# sherpa_1a_minimal_template.net
KiCad netlist of a schematic drawn in Altium Designer
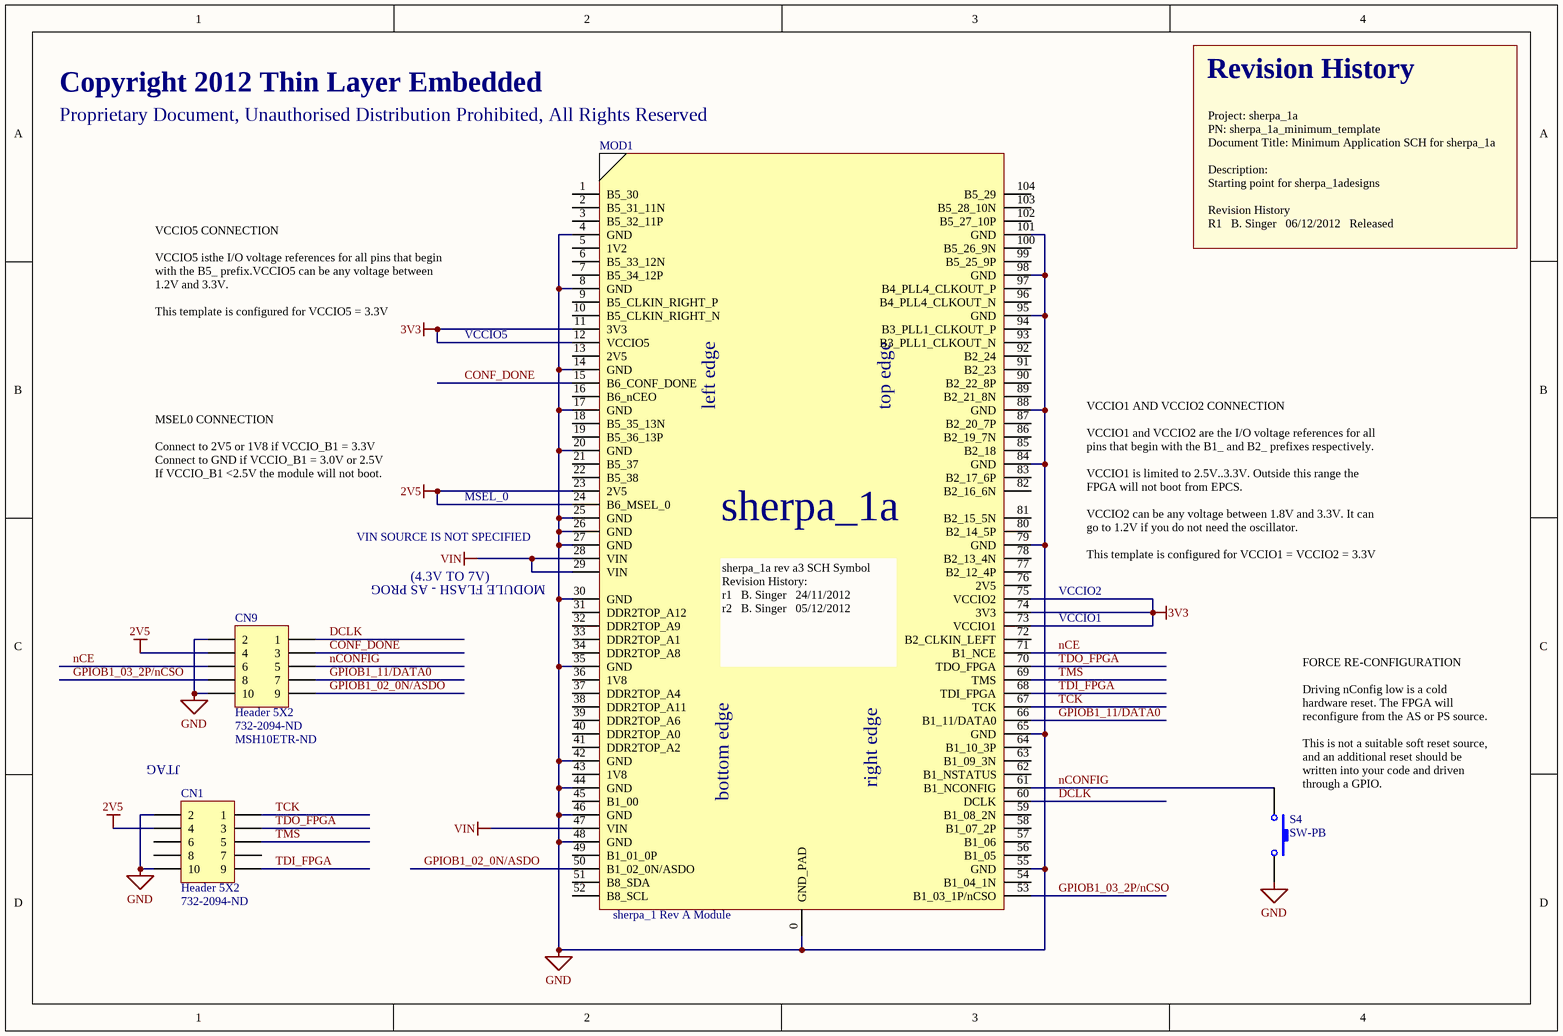
[diagram p0: sherpa_1a_minimal_template.SchDoc]

(export (version "E")
  (design (tool "Eeschema 10.0.6"))
  (components
    (comp (ref "CN1")
      (value "Header 5X2")
      (footprint "BOXHDR2X5_SMT")
      (description "Header, 5-Pin, Dual row")
      (fields
        (field (name "SUPPLIER PART NUMBER 1") "732-2094-ND")
        (field (name "MANUFACTURER") "Wurth Electronics Inc")
        (field (name "MANUFACTURER PART NUMBER") "61201021621")
        (field (name "PUBLISHER") "Altium Limited")
      )
      (libsource (lib "Miscellaneous Connectors") (part "Header 5X2"))
    )
    (comp (ref "CN9")
      (value "Header 5X2")
      (footprint "BOXHDR2X5_SMT")
      (description "Header, 5-Pin, Dual row")
      (fields
        (field (name "SUPPLIER PART NUMBER 1") "732-2094-ND")
        (field (name "MANUFACTURER") "Wurth Electronics Inc")
        (field (name "MANUFACTURER PART NUMBER") "61201021621")
        (field (name "SUPPLIER PART NUMBER 2") "MSH10ETR-ND")
        (field (name "PUBLISHER") "Altium Limited")
      )
      (libsource (lib "Miscellaneous Connectors") (part "Header 5X2"))
    )
    (comp (ref "MOD1")
      (value "sherpa_1 Rev A Module")
      (footprint "MODULE")
      (libsource (lib "master_library") (part "sherpa_1 Rev A Module"))
    )
    (comp (ref "S4")
      (value "SW-PB")
      (footprint "TL1105_V")
      (description "Switch")
      (fields (field (name "PUBLISHER") "Altium Limited"))
      (libsource (lib "Miscellaneous Devices") (part "SW-PB"))
    )
  )
  (nets
    (net (code "1") (name "/CONF_DONE") (class "Default")
      (node (ref "CN9") (pin "3") (pinfunction "3_3") (pintype "passive"))
      (node (ref "MOD1") (pin "15") (pinfunction "B6_CONF_DONE_15") (pintype "passive"))
    )
    (net (code "2") (name "/DCLK") (class "Default")
      (node (ref "CN9") (pin "1") (pinfunction "1_1") (pintype "passive"))
      (node (ref "MOD1") (pin "60") (pinfunction "DCLK_60") (pintype "passive"))
    )
    (net (code "3") (name "/GPIOB1_02_0N{slash}ASDO") (class "Default")
      (node (ref "CN9") (pin "9") (pinfunction "9_9") (pintype "passive"))
      (node (ref "MOD1") (pin "50") (pinfunction "B1_02_0N/ASDO_50") (pintype "passive"))
    )
    (net (code "4") (name "/GPIOB1_03_2P{slash}nCSO") (class "Default")
      (node (ref "CN9") (pin "8") (pinfunction "8_8") (pintype "passive"))
      (node (ref "MOD1") (pin "53") (pinfunction "B1_03_1P/nCSO_53") (pintype "passive"))
    )
    (net (code "5") (name "/GPIOB1_11{slash}DATA0") (class "Default")
      (node (ref "CN9") (pin "7") (pinfunction "7_7") (pintype "passive"))
      (node (ref "MOD1") (pin "66") (pinfunction "B1_11/DATA0_66") (pintype "passive"))
    )
    (net (code "6") (name "/TCK") (class "Default")
      (node (ref "CN1") (pin "1") (pinfunction "1_1") (pintype "passive"))
      (node (ref "MOD1") (pin "67") (pinfunction "TCK_67") (pintype "passive"))
    )
    (net (code "7") (name "/TDI_FPGA") (class "Default")
      (node (ref "CN1") (pin "9") (pinfunction "9_9") (pintype "passive"))
      (node (ref "MOD1") (pin "68") (pinfunction "TDI_FPGA_68") (pintype "passive"))
    )
    (net (code "8") (name "/TDO_FPGA") (class "Default")
      (node (ref "CN1") (pin "3") (pinfunction "3_3") (pintype "passive"))
      (node (ref "MOD1") (pin "70") (pinfunction "TDO_FPGA_70") (pintype "passive"))
    )
    (net (code "9") (name "/TMS") (class "Default")
      (node (ref "CN1") (pin "5") (pinfunction "5_5") (pintype "passive"))
      (node (ref "MOD1") (pin "69") (pinfunction "TMS_69") (pintype "passive"))
    )
    (net (code "10") (name "/nCE") (class "Default")
      (node (ref "CN9") (pin "6") (pinfunction "6_6") (pintype "passive"))
      (node (ref "MOD1") (pin "71") (pinfunction "B1_NCE_71") (pintype "passive"))
    )
    (net (code "11") (name "/nCONFIG") (class "Default")
      (node (ref "CN9") (pin "5") (pinfunction "5_5") (pintype "passive"))
      (node (ref "MOD1") (pin "61") (pinfunction "B1_NCONFIG_61") (pintype "passive"))
      (node (ref "S4") (pin "2") (pinfunction "2_2") (pintype "passive"))
    )
    (net (code "12") (name "2V5") (class "Default")
      (node (ref "CN1") (pin "4") (pinfunction "4_4") (pintype "passive"))
      (node (ref "CN9") (pin "4") (pinfunction "4_4") (pintype "passive"))
      (node (ref "MOD1") (pin "23") (pinfunction "2V5_23") (pintype "passive"))
      (node (ref "MOD1") (pin "24") (pinfunction "B6_MSEL_0_24") (pintype "passive"))
    )
    (net (code "13") (name "3V3") (class "Default")
      (node (ref "MOD1") (pin "11") (pinfunction "3V3_11") (pintype "passive"))
      (node (ref "MOD1") (pin "12") (pinfunction "VCCIO5_12") (pintype "passive"))
      (node (ref "MOD1") (pin "73") (pinfunction "VCCIO1_73") (pintype "passive"))
      (node (ref "MOD1") (pin "74") (pinfunction "3V3_74") (pintype "passive"))
      (node (ref "MOD1") (pin "75") (pinfunction "VCCIO2_75") (pintype "passive"))
    )
    (net (code "14") (name "GND") (class "Default")
      (node (ref "CN1") (pin "10") (pinfunction "10_10") (pintype "passive"))
      (node (ref "CN1") (pin "2") (pinfunction "2_2") (pintype "passive"))
      (node (ref "CN9") (pin "10") (pinfunction "10_10") (pintype "passive"))
      (node (ref "CN9") (pin "2") (pinfunction "2_2") (pintype "passive"))
      (node (ref "MOD1") (pin "0") (pinfunction "GND_PAD_0") (pintype "passive"))
      (node (ref "MOD1") (pin "101") (pinfunction "GND_101") (pintype "passive"))
      (node (ref "MOD1") (pin "14") (pinfunction "GND_14") (pintype "passive"))
      (node (ref "MOD1") (pin "17") (pinfunction "GND_17") (pintype "passive"))
      (node (ref "MOD1") (pin "20") (pinfunction "GND_20") (pintype "passive"))
      (node (ref "MOD1") (pin "25") (pinfunction "GND_25") (pintype "passive"))
      (node (ref "MOD1") (pin "26") (pinfunction "GND_26") (pintype "passive"))
      (node (ref "MOD1") (pin "27") (pinfunction "GND_27") (pintype "passive"))
      (node (ref "MOD1") (pin "30") (pinfunction "GND_30") (pintype "passive"))
      (node (ref "MOD1") (pin "35") (pinfunction "GND_35") (pintype "passive"))
      (node (ref "MOD1") (pin "4") (pinfunction "GND_4") (pintype "passive"))
      (node (ref "MOD1") (pin "42") (pinfunction "GND_42") (pintype "passive"))
      (node (ref "MOD1") (pin "44") (pinfunction "GND_44") (pintype "passive"))
      (node (ref "MOD1") (pin "46") (pinfunction "GND_46") (pintype "passive"))
      (node (ref "MOD1") (pin "48") (pinfunction "GND_48") (pintype "passive"))
      (node (ref "MOD1") (pin "55") (pinfunction "GND_55") (pintype "passive"))
      (node (ref "MOD1") (pin "65") (pinfunction "GND_65") (pintype "passive"))
      (node (ref "MOD1") (pin "79") (pinfunction "GND_79") (pintype "passive"))
      (node (ref "MOD1") (pin "8") (pinfunction "GND_8") (pintype "passive"))
      (node (ref "MOD1") (pin "84") (pinfunction "GND_84") (pintype "passive"))
      (node (ref "MOD1") (pin "88") (pinfunction "GND_88") (pintype "passive"))
      (node (ref "MOD1") (pin "95") (pinfunction "GND_95") (pintype "passive"))
      (node (ref "MOD1") (pin "98") (pinfunction "GND_98") (pintype "passive"))
      (node (ref "S4") (pin "1") (pinfunction "1_1") (pintype "passive"))
    )
    (net (code "15") (name "VIN") (class "Default")
      (node (ref "MOD1") (pin "28") (pinfunction "VIN_28") (pintype "passive"))
      (node (ref "MOD1") (pin "29") (pinfunction "VIN_29") (pintype "passive"))
      (node (ref "MOD1") (pin "47") (pinfunction "VIN_47") (pintype "passive"))
    )
    (net (code "16") (name "unconnected-(CN1-Pad6)") (class "Default")
      (node (ref "CN1") (pin "6") (pinfunction "6_6") (pintype "passive"))
    )
    (net (code "17") (name "unconnected-(CN1-Pad7)") (class "Default")
      (node (ref "CN1") (pin "7") (pinfunction "7_7") (pintype "passive"))
    )
    (net (code "18") (name "unconnected-(CN1-Pad8)") (class "Default")
      (node (ref "CN1") (pin "8") (pinfunction "8_8") (pintype "passive"))
    )
    (net (code "19") (name "unconnected-(MOD1-1V2-Pad5)") (class "Default")
      (node (ref "MOD1") (pin "5") (pinfunction "1V2_5") (pintype "passive"))
    )
    (net (code "20") (name "unconnected-(MOD1-1V8-Pad36)") (class "Default")
      (node (ref "MOD1") (pin "36") (pinfunction "1V8_36") (pintype "passive"))
    )
    (net (code "21") (name "unconnected-(MOD1-1V8-Pad43)") (class "Default")
      (node (ref "MOD1") (pin "43") (pinfunction "1V8_43") (pintype "passive"))
    )
    (net (code "22") (name "unconnected-(MOD1-2V5-Pad13)") (class "Default")
      (node (ref "MOD1") (pin "13") (pinfunction "2V5_13") (pintype "passive"))
    )
    (net (code "23") (name "unconnected-(MOD1-2V5-Pad76)") (class "Default")
      (node (ref "MOD1") (pin "76") (pinfunction "2V5_76") (pintype "passive"))
    )
    (net (code "24") (name "unconnected-(MOD1-B1_00-Pad45)") (class "Default")
      (node (ref "MOD1") (pin "45") (pinfunction "B1_00_45") (pintype "passive"))
    )
    (net (code "25") (name "unconnected-(MOD1-B1_01_0P-Pad49)") (class "Default")
      (node (ref "MOD1") (pin "49") (pinfunction "B1_01_0P_49") (pintype "passive"))
    )
    (net (code "26") (name "unconnected-(MOD1-B1_04_1N-Pad54)") (class "Default")
      (node (ref "MOD1") (pin "54") (pinfunction "B1_04_1N_54") (pintype "passive"))
    )
    (net (code "27") (name "unconnected-(MOD1-B1_05-Pad56)") (class "Default")
      (node (ref "MOD1") (pin "56") (pinfunction "B1_05_56") (pintype "passive"))
    )
    (net (code "28") (name "unconnected-(MOD1-B1_06-Pad57)") (class "Default")
      (node (ref "MOD1") (pin "57") (pinfunction "B1_06_57") (pintype "passive"))
    )
    (net (code "29") (name "unconnected-(MOD1-B1_07_2P-Pad58)") (class "Default")
      (node (ref "MOD1") (pin "58") (pinfunction "B1_07_2P_58") (pintype "passive"))
    )
    (net (code "30") (name "unconnected-(MOD1-B1_08_2N-Pad59)") (class "Default")
      (node (ref "MOD1") (pin "59") (pinfunction "B1_08_2N_59") (pintype "passive"))
    )
    (net (code "31") (name "unconnected-(MOD1-B1_09_3N-Pad63)") (class "Default")
      (node (ref "MOD1") (pin "63") (pinfunction "B1_09_3N_63") (pintype "passive"))
    )
    (net (code "32") (name "unconnected-(MOD1-B1_10_3P-Pad64)") (class "Default")
      (node (ref "MOD1") (pin "64") (pinfunction "B1_10_3P_64") (pintype "passive"))
    )
    (net (code "33") (name "unconnected-(MOD1-B1_NSTATUS-Pad62)") (class "Default")
      (node (ref "MOD1") (pin "62") (pinfunction "B1_NSTATUS_62") (pintype "passive"))
    )
    (net (code "34") (name "unconnected-(MOD1-B2_12_4P-Pad77)") (class "Default")
      (node (ref "MOD1") (pin "77") (pinfunction "B2_12_4P_77") (pintype "passive"))
    )
    (net (code "35") (name "unconnected-(MOD1-B2_13_4N-Pad78)") (class "Default")
      (node (ref "MOD1") (pin "78") (pinfunction "B2_13_4N_78") (pintype "passive"))
    )
    (net (code "36") (name "unconnected-(MOD1-B2_14_5P-Pad80)") (class "Default")
      (node (ref "MOD1") (pin "80") (pinfunction "B2_14_5P_80") (pintype "passive"))
    )
    (net (code "37") (name "unconnected-(MOD1-B2_15_5N-Pad81)") (class "Default")
      (node (ref "MOD1") (pin "81") (pinfunction "B2_15_5N_81") (pintype "passive"))
    )
    (net (code "38") (name "unconnected-(MOD1-B2_16_6N-Pad82)") (class "Default")
      (node (ref "MOD1") (pin "82") (pinfunction "B2_16_6N_82") (pintype "passive"))
    )
    (net (code "39") (name "unconnected-(MOD1-B2_17_6P-Pad83)") (class "Default")
      (node (ref "MOD1") (pin "83") (pinfunction "B2_17_6P_83") (pintype "passive"))
    )
    (net (code "40") (name "unconnected-(MOD1-B2_18-Pad85)") (class "Default")
      (node (ref "MOD1") (pin "85") (pinfunction "B2_18_85") (pintype "passive"))
    )
    (net (code "41") (name "unconnected-(MOD1-B2_19_7N-Pad86)") (class "Default")
      (node (ref "MOD1") (pin "86") (pinfunction "B2_19_7N_86") (pintype "passive"))
    )
    (net (code "42") (name "unconnected-(MOD1-B2_20_7P-Pad87)") (class "Default")
      (node (ref "MOD1") (pin "87") (pinfunction "B2_20_7P_87") (pintype "passive"))
    )
    (net (code "43") (name "unconnected-(MOD1-B2_21_8N-Pad89)") (class "Default")
      (node (ref "MOD1") (pin "89") (pinfunction "B2_21_8N_89") (pintype "passive"))
    )
    (net (code "44") (name "unconnected-(MOD1-B2_22_8P-Pad90)") (class "Default")
      (node (ref "MOD1") (pin "90") (pinfunction "B2_22_8P_90") (pintype "passive"))
    )
    (net (code "45") (name "unconnected-(MOD1-B2_23-Pad91)") (class "Default")
      (node (ref "MOD1") (pin "91") (pinfunction "B2_23_91") (pintype "passive"))
    )
    (net (code "46") (name "unconnected-(MOD1-B2_24-Pad92)") (class "Default")
      (node (ref "MOD1") (pin "92") (pinfunction "B2_24_92") (pintype "passive"))
    )
    (net (code "47") (name "unconnected-(MOD1-B2_CLKIN_LEFT-Pad72)") (class "Default")
      (node (ref "MOD1") (pin "72") (pinfunction "B2_CLKIN_LEFT_72") (pintype "passive"))
    )
    (net (code "48") (name "unconnected-(MOD1-B3_PLL1_CLKOUT_N-Pad93)") (class "Default")
      (node (ref "MOD1") (pin "93") (pinfunction "B3_PLL1_CLKOUT_N_93") (pintype "passive"))
    )
    (net (code "49") (name "unconnected-(MOD1-B3_PLL1_CLKOUT_P-Pad94)") (class "Default")
      (node (ref "MOD1") (pin "94") (pinfunction "B3_PLL1_CLKOUT_P_94") (pintype "passive"))
    )
    (net (code "50") (name "unconnected-(MOD1-B4_PLL4_CLKOUT_N-Pad96)") (class "Default")
      (node (ref "MOD1") (pin "96") (pinfunction "B4_PLL4_CLKOUT_N_96") (pintype "passive"))
    )
    (net (code "51") (name "unconnected-(MOD1-B4_PLL4_CLKOUT_P-Pad97)") (class "Default")
      (node (ref "MOD1") (pin "97") (pinfunction "B4_PLL4_CLKOUT_P_97") (pintype "passive"))
    )
    (net (code "52") (name "unconnected-(MOD1-B5_25_9P-Pad99)") (class "Default")
      (node (ref "MOD1") (pin "99") (pinfunction "B5_25_9P_99") (pintype "passive"))
    )
    (net (code "53") (name "unconnected-(MOD1-B5_26_9N-Pad100)") (class "Default")
      (node (ref "MOD1") (pin "100") (pinfunction "B5_26_9N_100") (pintype "passive"))
    )
    (net (code "54") (name "unconnected-(MOD1-B5_27_10P-Pad102)") (class "Default")
      (node (ref "MOD1") (pin "102") (pinfunction "B5_27_10P_102") (pintype "passive"))
    )
    (net (code "55") (name "unconnected-(MOD1-B5_28_10N-Pad103)") (class "Default")
      (node (ref "MOD1") (pin "103") (pinfunction "B5_28_10N_103") (pintype "passive"))
    )
    (net (code "56") (name "unconnected-(MOD1-B5_29-Pad104)") (class "Default")
      (node (ref "MOD1") (pin "104") (pinfunction "B5_29_104") (pintype "passive"))
    )
    (net (code "57") (name "unconnected-(MOD1-B5_30-Pad1)") (class "Default")
      (node (ref "MOD1") (pin "1") (pinfunction "B5_30_1") (pintype "passive"))
    )
    (net (code "58") (name "unconnected-(MOD1-B5_31_11N-Pad2)") (class "Default")
      (node (ref "MOD1") (pin "2") (pinfunction "B5_31_11N_2") (pintype "passive"))
    )
    (net (code "59") (name "unconnected-(MOD1-B5_32_11P-Pad3)") (class "Default")
      (node (ref "MOD1") (pin "3") (pinfunction "B5_32_11P_3") (pintype "passive"))
    )
    (net (code "60") (name "unconnected-(MOD1-B5_33_12N-Pad6)") (class "Default")
      (node (ref "MOD1") (pin "6") (pinfunction "B5_33_12N_6") (pintype "passive"))
    )
    (net (code "61") (name "unconnected-(MOD1-B5_34_12P-Pad7)") (class "Default")
      (node (ref "MOD1") (pin "7") (pinfunction "B5_34_12P_7") (pintype "passive"))
    )
    (net (code "62") (name "unconnected-(MOD1-B5_35_13N-Pad18)") (class "Default")
      (node (ref "MOD1") (pin "18") (pinfunction "B5_35_13N_18") (pintype "passive"))
    )
    (net (code "63") (name "unconnected-(MOD1-B5_36_13P-Pad19)") (class "Default")
      (node (ref "MOD1") (pin "19") (pinfunction "B5_36_13P_19") (pintype "passive"))
    )
    (net (code "64") (name "unconnected-(MOD1-B5_37-Pad21)") (class "Default")
      (node (ref "MOD1") (pin "21") (pinfunction "B5_37_21") (pintype "passive"))
    )
    (net (code "65") (name "unconnected-(MOD1-B5_38-Pad22)") (class "Default")
      (node (ref "MOD1") (pin "22") (pinfunction "B5_38_22") (pintype "passive"))
    )
    (net (code "66") (name "unconnected-(MOD1-B5_CLKIN_RIGHT_N-Pad10)") (class "Default")
      (node (ref "MOD1") (pin "10") (pinfunction "B5_CLKIN_RIGHT_N_10") (pintype "passive"))
    )
    (net (code "67") (name "unconnected-(MOD1-B5_CLKIN_RIGHT_P-Pad9)") (class "Default")
      (node (ref "MOD1") (pin "9") (pinfunction "B5_CLKIN_RIGHT_P_9") (pintype "passive"))
    )
    (net (code "68") (name "unconnected-(MOD1-B6_nCEO-Pad16)") (class "Default")
      (node (ref "MOD1") (pin "16") (pinfunction "B6_nCEO_16") (pintype "passive"))
    )
    (net (code "69") (name "unconnected-(MOD1-B8_SCL-Pad52)") (class "Default")
      (node (ref "MOD1") (pin "52") (pinfunction "B8_SCL_52") (pintype "passive"))
    )
    (net (code "70") (name "unconnected-(MOD1-B8_SDA-Pad51)") (class "Default")
      (node (ref "MOD1") (pin "51") (pinfunction "B8_SDA_51") (pintype "passive"))
    )
    (net (code "71") (name "unconnected-(MOD1-DDR2TOP_A0-Pad40)") (class "Default")
      (node (ref "MOD1") (pin "40") (pinfunction "DDR2TOP_A0_40") (pintype "passive"))
    )
    (net (code "72") (name "unconnected-(MOD1-DDR2TOP_A1-Pad33)") (class "Default")
      (node (ref "MOD1") (pin "33") (pinfunction "DDR2TOP_A1_33") (pintype "passive"))
    )
    (net (code "73") (name "unconnected-(MOD1-DDR2TOP_A2-Pad41)") (class "Default")
      (node (ref "MOD1") (pin "41") (pinfunction "DDR2TOP_A2_41") (pintype "passive"))
    )
    (net (code "74") (name "unconnected-(MOD1-DDR2TOP_A4-Pad37)") (class "Default")
      (node (ref "MOD1") (pin "37") (pinfunction "DDR2TOP_A4_37") (pintype "passive"))
    )
    (net (code "75") (name "unconnected-(MOD1-DDR2TOP_A6-Pad39)") (class "Default")
      (node (ref "MOD1") (pin "39") (pinfunction "DDR2TOP_A6_39") (pintype "passive"))
    )
    (net (code "76") (name "unconnected-(MOD1-DDR2TOP_A8-Pad34)") (class "Default")
      (node (ref "MOD1") (pin "34") (pinfunction "DDR2TOP_A8_34") (pintype "passive"))
    )
    (net (code "77") (name "unconnected-(MOD1-DDR2TOP_A9-Pad32)") (class "Default")
      (node (ref "MOD1") (pin "32") (pinfunction "DDR2TOP_A9_32") (pintype "passive"))
    )
    (net (code "78") (name "unconnected-(MOD1-DDR2TOP_A11-Pad38)") (class "Default")
      (node (ref "MOD1") (pin "38") (pinfunction "DDR2TOP_A11_38") (pintype "passive"))
    )
    (net (code "79") (name "unconnected-(MOD1-DDR2TOP_A12-Pad31)") (class "Default")
      (node (ref "MOD1") (pin "31") (pinfunction "DDR2TOP_A12_31") (pintype "passive"))
    )
  )
)
